# trippot.net
KiCad netlist of a schematic drawn in Altium Designer
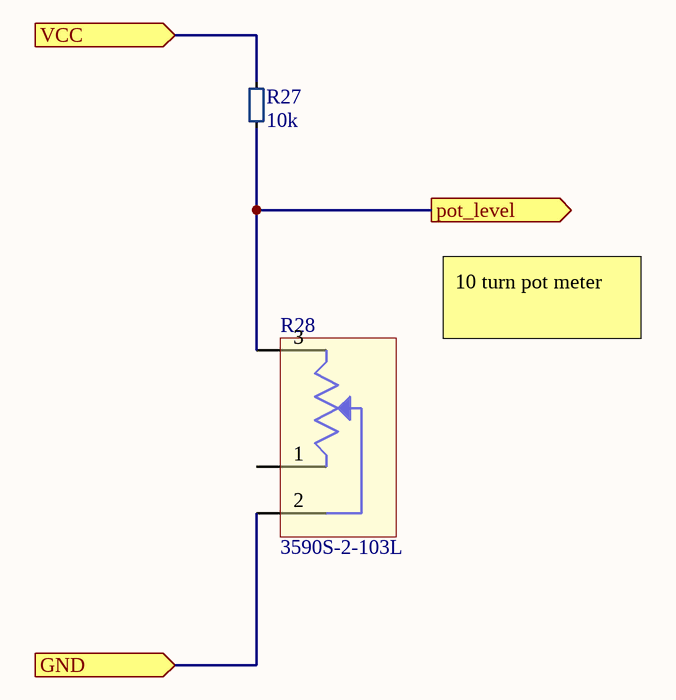
[diagram p0: trippot.SchDoc]

(export (version "E")
  (design (tool "Eeschema 10.0.6"))
  (components
    (comp (ref "R27")
      (value "RC0402FR-0710KL")
      (footprint "SMD_0402(1005)_M")
      (description "Surface Mount Thick Film Resistor, Rc Series, 10 Kohm, 62.5 Mw, - 1%, 50 V, 0402 [1005 Metric]")
      (fields (field (name "RESISTANCE") "10k") (field (name "TOLERANCE") "1%"))
      (libsource (lib "concord server") (part "resistor_european"))
    )
    (comp (ref "R28")
      (value "3590S-2-103L")
      (footprint "3590S-2-103L-Footprint-1")
      (fields (field (name "TOLERANCE") "5%"))
      (libsource (lib "concord server") (part "3590S-2-103L"))
    )
  )
  (nets
    (net (code "1") (name "/GND") (class "Default")
      (node (ref "R28") (pin "2") (pinfunction "2_2") (pintype "passive"))
    )
    (net (code "2") (name "/VCC") (class "Default")
      (node (ref "R27") (pin "2") (pinfunction "2_2") (pintype "passive"))
    )
    (net (code "3") (name "/pot_level") (class "Default")
      (node (ref "R27") (pin "1") (pinfunction "1_1") (pintype "passive"))
      (node (ref "R28") (pin "3") (pinfunction "3_3") (pintype "passive"))
    )
    (net (code "4") (name "unconnected-(R28-13-Pad1)") (class "Default")
      (node (ref "R28") (pin "1") (pinfunction "13_1") (pintype "passive"))
    )
  )
)
